# LoopDriver.net
KiCad netlist of a schematic drawn in Altium Designer
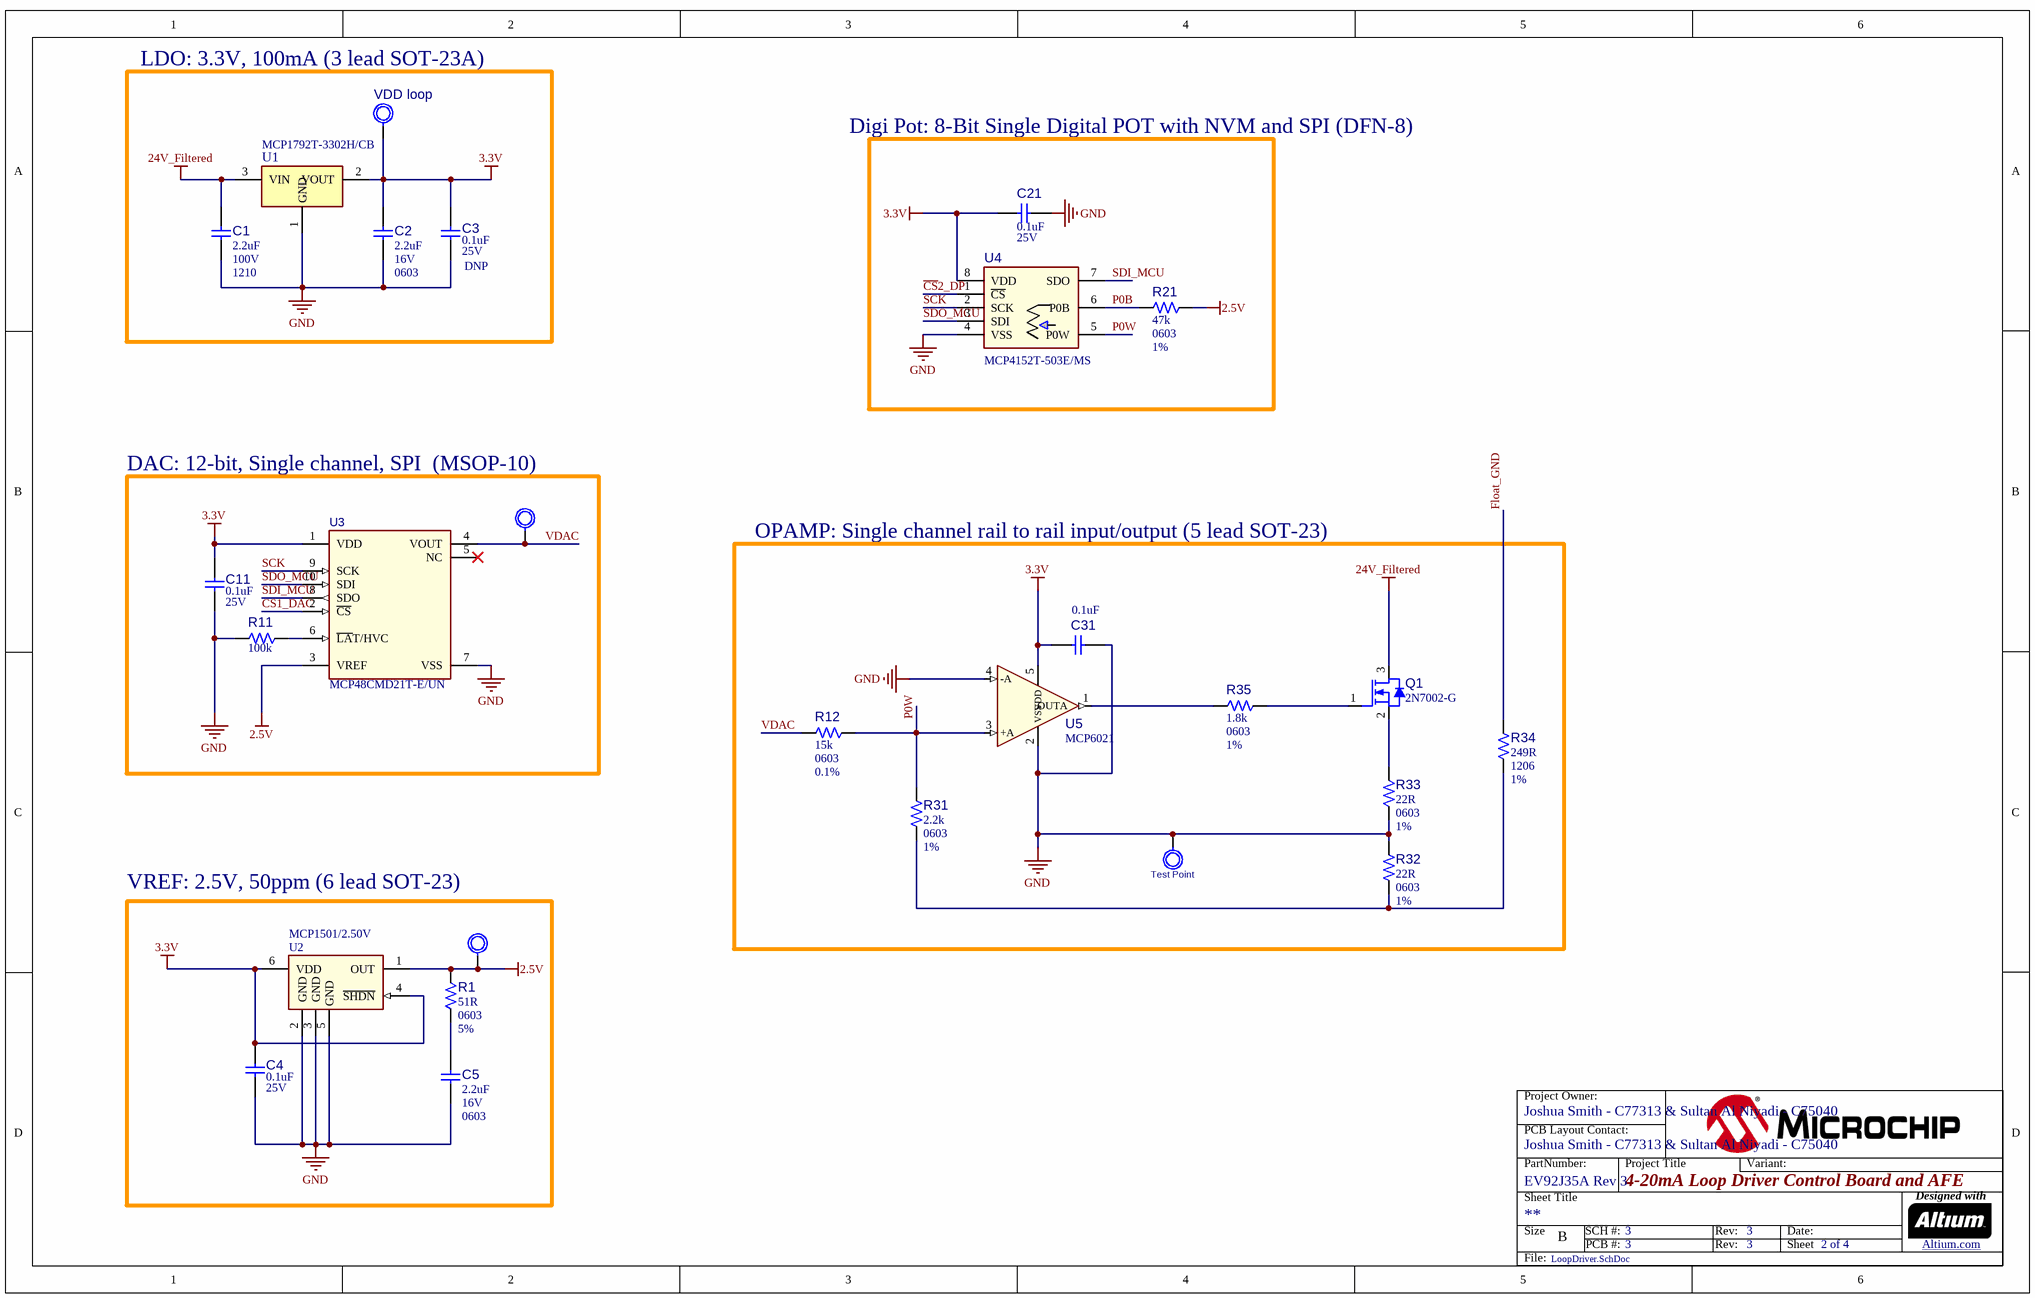
[diagram p0: LoopDriver.SchDoc]

(export (version "E")
  (design (tool "Eeschema 10.0.6"))
  (components
    (comp (ref "C1")
      (value "2.2uF")
      (footprint "CAP_C_1210")
      (fields
        (field (name "VOLTAGE") "100V")
        (field (name "PACKAGE") "1210")
        (field (name "TOLERANCE") "10%")
        (field (name "OWNER") "Narasimha Murthy")
      )
      (libsource (lib "MCL-Offline") (part "Capacitor NP"))
    )
    (comp (ref "C2")
      (value "2.2uF")
      (footprint "CAP_C_0603")
      (fields (field (name "VOLTAGE") "16V") (field (name "PACKAGE") "0603") (field (name "TOLERANCE") "10%"))
      (libsource (lib "MCL-Offline") (part "Capacitor NP"))
    )
    (comp (ref "C3")
      (value "0.1uF")
      (footprint "CAP_C_0603")
      (fields
        (field (name "VOLTAGE") "25V")
        (field (name "TOLERANCE") "10%")
        (field (name "POPULATED") "DNP")
        (field (name "OWNER") "Cristina Salanti")
      )
      (libsource (lib "MCL-Offline") (part "Capacitor NP"))
    )
    (comp (ref "C4")
      (value "0.1uF")
      (footprint "CAP_C_0603")
      (fields
        (field (name "VOLTAGE") "25V")
        (field (name "TOLERANCE") "10%")
        (field (name "OWNER") "Cristina Salanti")
      )
      (libsource (lib "MCL-Offline") (part "Capacitor NP"))
    )
    (comp (ref "C5")
      (value "2.2uF")
      (footprint "CAP_C_0603")
      (fields (field (name "VOLTAGE") "16V") (field (name "PACKAGE") "0603") (field (name "TOLERANCE") "10%"))
      (libsource (lib "MCL-Offline") (part "Capacitor NP"))
    )
    (comp (ref "C11")
      (value "0.1uF")
      (footprint "CAP_C_0603")
      (fields
        (field (name "VOLTAGE") "25V")
        (field (name "TOLERANCE") "10%")
        (field (name "OWNER") "Cristina Salanti")
      )
      (libsource (lib "MCL-Offline") (part "Capacitor NP"))
    )
    (comp (ref "C21")
      (value "0.1uF")
      (footprint "CAP_C_0603")
      (fields
        (field (name "VOLTAGE") "25V")
        (field (name "TOLERANCE") "10%")
        (field (name "OWNER") "Cristina Salanti")
      )
      (libsource (lib "MCL-Offline") (part "Capacitor NP"))
    )
    (comp (ref "C31")
      (value "0.1uF")
      (footprint "CAP_C_0603")
      (fields
        (field (name "VOLTAGE") "25V")
        (field (name "TOLERANCE") "10%")
        (field (name "OWNER") "Cristina Salanti")
      )
      (libsource (lib "MCL-Offline") (part "Capacitor NP"))
    )
    (comp (ref "GND")
      (value "Test Point")
      (footprint "CON_TP_TH_V_BLK_KEC_5011")
      (fields (field (name "OWNER") "Tad Ahlvers"))
      (libsource (lib "MCL-Offline") (part "Test Point"))
    )
    (comp (ref "Q1")
      (value "2N7002-G")
      (footprint "SOT-23-3")
      (description "Transistor MOS")
      (fields (field (name "OWNER") "Mark Loper"))
      (libsource (lib "MCL-Offline") (part "Transistor MOS-N GSD"))
    )
    (comp (ref "R1")
      (value "51R")
      (footprint "RES_C_0603")
      (description "Resistor")
      (fields (field (name "PACKAGE") "0603") (field (name "TOLERANCE") "5%") (field (name "POWER") "1/10W"))
      (libsource (lib "MCL-Offline") (part "Resistor"))
    )
    (comp (ref "R11")
      (value "100k")
      (footprint "RES_C_0603")
      (description "Resistor")
      (fields (field (name "TOLERANCE") "5%") (field (name "VOLTAGE") "75V"))
      (libsource (lib "MCL-Offline") (part "Resistor"))
    )
    (comp (ref "R12")
      (value "15k")
      (footprint "RES_C_0603")
      (description "Resistor")
      (fields
        (field (name "PACKAGE") "0603")
        (field (name "TOLERANCE") "0.1%")
        (field (name "POWER") "0.1W, 1/10W")
        (field (name "OWNER") "Jose Garcia")
      )
      (libsource (lib "MCL-Offline") (part "Resistor"))
    )
    (comp (ref "R21")
      (value "47k")
      (footprint "RES_C_0603")
      (description "Resistor")
      (fields
        (field (name "PACKAGE") "0603")
        (field (name "TOLERANCE") "1%")
        (field (name "VOLTAGE") "75V")
        (field (name "POWER") "1/10W")
        (field (name "OWNER") "Adrian M (M91404)")
      )
      (libsource (lib "MCL-Offline") (part "Resistor"))
    )
    (comp (ref "R31")
      (value "2.2k")
      (footprint "RES_C_0603")
      (description "Resistor")
      (fields
        (field (name "PACKAGE") "0603")
        (field (name "TOLERANCE") "1%")
        (field (name "VOLTAGE") "75V")
        (field (name "POWER") "1/10W")
        (field (name "OWNER") "Bogdan P (M91398)")
      )
      (libsource (lib "MCL-Offline") (part "Resistor"))
    )
    (comp (ref "R32")
      (value "22R")
      (footprint "RES_C_0603")
      (description "Resistor")
      (fields
        (field (name "PACKAGE") "0603")
        (field (name "TOLERANCE") "1%")
        (field (name "VOLTAGE") "75V")
        (field (name "POWER") "1/10W")
      )
      (libsource (lib "MCL-Offline") (part "Resistor"))
    )
    (comp (ref "R33")
      (value "22R")
      (footprint "RES_C_0603")
      (description "Resistor")
      (fields
        (field (name "PACKAGE") "0603")
        (field (name "TOLERANCE") "1%")
        (field (name "VOLTAGE") "75V")
        (field (name "POWER") "1/10W")
      )
      (libsource (lib "MCL-Offline") (part "Resistor"))
    )
    (comp (ref "R34")
      (value "249R")
      (footprint "RES_C_1206")
      (description "Resistor")
      (fields
        (field (name "PACKAGE") "1206")
        (field (name "TOLERANCE") "1%")
        (field (name "VOLTAGE") "200V")
        (field (name "POWER") "1/4W")
      )
      (libsource (lib "MCL-Offline") (part "Resistor"))
    )
    (comp (ref "R35")
      (value "1.8k")
      (footprint "RES_C_0603")
      (description "Resistor")
      (fields
        (field (name "PACKAGE") "0603")
        (field (name "TOLERANCE") "1%")
        (field (name "VOLTAGE") "75V")
        (field (name "POWER") "1/10W")
        (field (name "OWNER") "Bogdan P (M91398)")
      )
      (libsource (lib "MCL-Offline") (part "Resistor"))
    )
    (comp (ref "U1")
      (value "MCP1792T-3302H/CB")
      (footprint "SOT-23A-3")
      (description "LDO")
      (fields (field (name "OWNER") "Cristina Salanti"))
      (libsource (lib "MCL-Offline") (part "MCP1754S SOT-23A-3"))
    )
    (comp (ref "U2")
      (value "MCP1501/2.50V")
      (footprint "SOT-23-6")
      (description "High-Precision Buffered Voltage Reference")
      (fields (field (name "OWNER") "Jose Garcia"))
      (libsource (lib "MCL-Offline") (part "MCP1501 SOT-23-6"))
    )
    (comp (ref "U3")
      (value "MCP48CMD21T-E/UN")
      (footprint "MSOP-10")
      (fields (field (name "OWNER") "Alexandru Chiser"))
      (libsource (lib "MCL-Offline") (part "MCP48CXDX1_MSOP-10"))
    )
    (comp (ref "U4")
      (value "MCP4152T-503E/MS")
      (footprint "MSOP-8")
      (fields (field (name "OWNER") "Jose Garcia"))
      (libsource (lib "MCL-Offline") (part "MCP41X2 SOIC-8_PDIP-8_MSOP-8"))
    )
    (comp (ref "U5")
      (value "MCP6021")
      (footprint "SOT-23-5")
      (description "OPAMP")
      (libsource (lib "MCL-Offline") (part "MCP6XX1_6 SOT-23-5_SC-70-5"))
    )
    (comp (ref "VDAC")
      (value "~")
      (footprint "CON_TP_TH_V_RED_KEC_5010")
      (description "Test Point")
      (fields (field (name "OWNER") "Stephen Humberd"))
      (libsource (lib "MCL-Offline") (part "Test Point"))
    )
    (comp (ref "VDD loop")
      (value "~")
      (footprint "CON_TP_TH_V_RED_KEC_5010")
      (description "Test Point")
      (fields (field (name "OWNER") "Stephen Humberd"))
      (libsource (lib "MCL-Offline") (part "Test Point"))
    )
    (comp (ref "VREF")
      (value "~")
      (footprint "CON_TP_TH_V_RED_KEC_5010")
      (description "Test Point")
      (fields (field (name "OWNER") "Stephen Humberd"))
      (libsource (lib "MCL-Offline") (part "Test Point"))
    )
  )
  (nets
    (net (code "1") (name "/Float_GND") (class "Default")
      (node (ref "R34") (pin "2") (pinfunction "2_2") (pintype "passive"))
    )
    (net (code "2") (name "/P0B") (class "Default")
      (node (ref "R21") (pin "2") (pinfunction "2_2") (pintype "passive"))
      (node (ref "U4") (pin "6") (pinfunction "P0B_6") (pintype "passive"))
    )
    (net (code "3") (name "/P0W") (class "Default")
      (node (ref "R12") (pin "2") (pinfunction "2_2") (pintype "passive"))
      (node (ref "R31") (pin "2") (pinfunction "2_2") (pintype "passive"))
      (node (ref "U4") (pin "5") (pinfunction "P0W_5") (pintype "passive"))
      (node (ref "U5") (pin "3") (pinfunction "+A_3") (pintype "input"))
    )
    (net (code "4") (name "/SCK") (class "Default")
      (node (ref "U3") (pin "9") (pinfunction "SCK_9") (pintype "input"))
      (node (ref "U4") (pin "2") (pinfunction "SCK_2") (pintype "passive"))
    )
    (net (code "5") (name "/SDI_MCU") (class "Default")
      (node (ref "U3") (pin "8") (pinfunction "SDO_8") (pintype "output"))
      (node (ref "U4") (pin "7") (pinfunction "SDO_7") (pintype "passive"))
    )
    (net (code "6") (name "/SDO_MCU") (class "Default")
      (node (ref "U3") (pin "10") (pinfunction "SDI_10") (pintype "input"))
      (node (ref "U4") (pin "3") (pinfunction "SDI_3") (pintype "passive"))
    )
    (net (code "7") (name "/VDAC") (class "Default")
      (node (ref "R12") (pin "1") (pinfunction "1_1") (pintype "passive"))
      (node (ref "U3") (pin "4") (pinfunction "VOUT_4") (pintype "passive"))
      (node (ref "VDAC") (pin "1") (pinfunction "1_1") (pintype "passive"))
    )
    (net (code "8") (name "/~{CS}1_DAC") (class "Default")
      (node (ref "U3") (pin "2") (pinfunction "~{CS}_2") (pintype "input"))
    )
    (net (code "9") (name "/~{CS}2_DP") (class "Default")
      (node (ref "U4") (pin "1") (pinfunction "~{CS}_1") (pintype "passive"))
    )
    (net (code "10") (name "2.5V") (class "Default")
      (node (ref "R1") (pin "2") (pinfunction "2_2") (pintype "passive"))
      (node (ref "R21") (pin "1") (pinfunction "1_1") (pintype "passive"))
      (node (ref "U2") (pin "1") (pinfunction "OUT_1") (pintype "power_in"))
      (node (ref "U3") (pin "3") (pinfunction "VREF_3") (pintype "passive"))
      (node (ref "VREF") (pin "1") (pinfunction "1_1") (pintype "passive"))
    )
    (net (code "11") (name "3.3V") (class "Default")
      (node (ref "C11") (pin "1") (pinfunction "1_1") (pintype "passive"))
      (node (ref "C2") (pin "2") (pinfunction "2_2") (pintype "passive"))
      (node (ref "C21") (pin "2") (pinfunction "2_2") (pintype "passive"))
      (node (ref "C3") (pin "2") (pinfunction "2_2") (pintype "passive"))
      (node (ref "C31") (pin "1") (pinfunction "1_1") (pintype "passive"))
      (node (ref "C4") (pin "1") (pinfunction "1_1") (pintype "passive"))
      (node (ref "U1") (pin "2") (pinfunction "VOUT_2") (pintype "power_in"))
      (node (ref "U2") (pin "4") (pinfunction "~{SHDN}_4") (pintype "input"))
      (node (ref "U2") (pin "6") (pinfunction "VDD_6") (pintype "power_in"))
      (node (ref "U3") (pin "1") (pinfunction "VDD_1") (pintype "power_in"))
      (node (ref "U4") (pin "8") (pinfunction "VDD_8") (pintype "passive"))
      (node (ref "U5") (pin "5") (pinfunction "VDD_5") (pintype "power_in"))
      (node (ref "VDD loop") (pin "1") (pinfunction "1_1") (pintype "passive"))
    )
    (net (code "12") (name "24V_Filtered") (class "Default")
      (node (ref "C1") (pin "2") (pinfunction "2_2") (pintype "passive"))
      (node (ref "Q1") (pin "3") (pinfunction "D_3") (pintype "passive"))
      (node (ref "U1") (pin "3") (pinfunction "VIN_3") (pintype "power_in"))
    )
    (net (code "13") (name "GND") (class "Default")
      (node (ref "C1") (pin "1") (pinfunction "1_1") (pintype "passive"))
      (node (ref "C11") (pin "2") (pinfunction "2_2") (pintype "passive"))
      (node (ref "C2") (pin "1") (pinfunction "1_1") (pintype "passive"))
      (node (ref "C21") (pin "1") (pinfunction "1_1") (pintype "passive"))
      (node (ref "C3") (pin "1") (pinfunction "1_1") (pintype "passive"))
      (node (ref "C31") (pin "2") (pinfunction "2_2") (pintype "passive"))
      (node (ref "C4") (pin "2") (pinfunction "2_2") (pintype "passive"))
      (node (ref "C5") (pin "1") (pinfunction "1_1") (pintype "passive"))
      (node (ref "GND") (pin "1") (pinfunction "1_1") (pintype "passive"))
      (node (ref "R11") (pin "1") (pinfunction "1_1") (pintype "passive"))
      (node (ref "R32") (pin "2") (pinfunction "2_2") (pintype "passive"))
      (node (ref "R33") (pin "1") (pinfunction "1_1") (pintype "passive"))
      (node (ref "U1") (pin "1") (pinfunction "GND_1") (pintype "power_in"))
      (node (ref "U2") (pin "2") (pinfunction "GND_2") (pintype "power_in"))
      (node (ref "U2") (pin "3") (pinfunction "GND_3") (pintype "power_in"))
      (node (ref "U2") (pin "5") (pinfunction "GND_5") (pintype "power_in"))
      (node (ref "U3") (pin "7") (pinfunction "VSS_7") (pintype "power_in"))
      (node (ref "U4") (pin "4") (pinfunction "VSS_4") (pintype "passive"))
      (node (ref "U5") (pin "2") (pinfunction "VSS_2") (pintype "power_in"))
      (node (ref "U5") (pin "4") (pinfunction "-A_4") (pintype "input"))
    )
    (net (code "14") (name "Net-(C5-Pad2)") (class "Default")
      (node (ref "C5") (pin "2") (pinfunction "2_2") (pintype "passive"))
      (node (ref "R1") (pin "1") (pinfunction "1_1") (pintype "passive"))
    )
    (net (code "15") (name "Net-(Q1-G)") (class "Default")
      (node (ref "Q1") (pin "1") (pinfunction "G_1") (pintype "passive"))
      (node (ref "R35") (pin "2") (pinfunction "2_2") (pintype "passive"))
    )
    (net (code "16") (name "Net-(Q1-S)") (class "Default")
      (node (ref "Q1") (pin "2") (pinfunction "S_2") (pintype "passive"))
      (node (ref "R33") (pin "2") (pinfunction "2_2") (pintype "passive"))
    )
    (net (code "17") (name "Net-(R31-Pad1)") (class "Default")
      (node (ref "R31") (pin "1") (pinfunction "1_1") (pintype "passive"))
      (node (ref "R32") (pin "1") (pinfunction "1_1") (pintype "passive"))
      (node (ref "R34") (pin "1") (pinfunction "1_1") (pintype "passive"))
    )
    (net (code "18") (name "Net-(U3-~{LA}T{slash}HVC)") (class "Default")
      (node (ref "R11") (pin "2") (pinfunction "2_2") (pintype "passive"))
      (node (ref "U3") (pin "6") (pinfunction "~{LA}T/HVC_6") (pintype "input"))
    )
    (net (code "19") (name "Net-(U5-OUTA)") (class "Default")
      (node (ref "R35") (pin "1") (pinfunction "1_1") (pintype "passive"))
      (node (ref "U5") (pin "1") (pinfunction "OUTA_1") (pintype "output"))
    )
    (net (code "20") (name "unconnected-(U3-NC-Pad5)") (class "Default")
      (node (ref "U3") (pin "5") (pinfunction "NC_5") (pintype "passive+no_connect"))
    )
  )
)
